# fatteningFarm.net
KiCad netlist of a schematic drawn in EAGLE
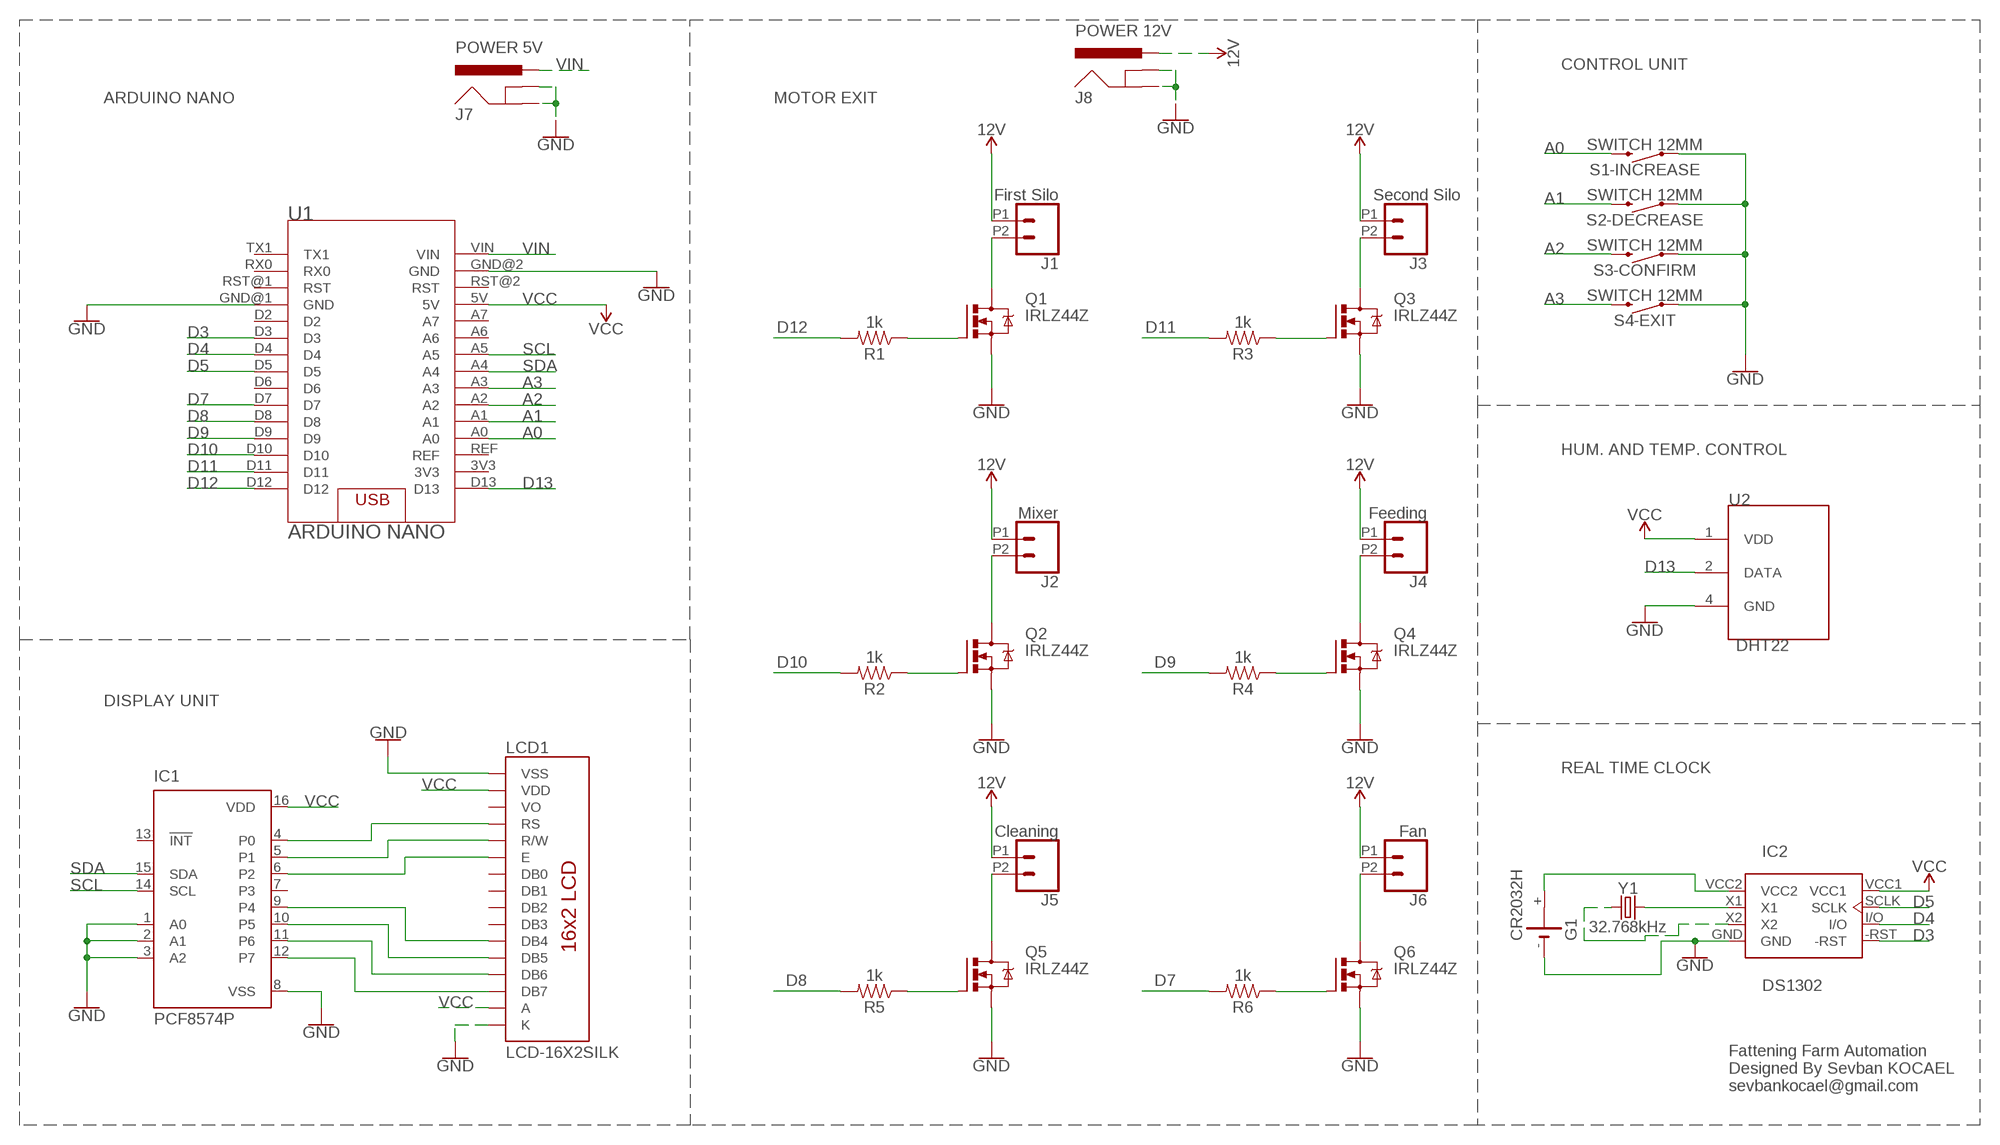
[diagram p0: schematic, sheet 1]

(export (version "E")
  (design (tool "Eeschema 10.0.6"))
  (components
    (comp (ref "G1")
      (value "CR2032H")
      (footprint "eagle-import:CR2032H")
      (libsource (lib "eagle-import") (part "CR2032H"))
    )
    (comp (ref "IC1")
      (value "PCF8574P")
      (footprint "eagle-import:DIL16")
      (fields (field (name "MPN") "PCF8574PN"))
      (libsource (lib "eagle-import") (part "PCF8574P"))
    )
    (comp (ref "IC2")
      (value "DS1302")
      (footprint "eagle-import:DIL08")
      (libsource (lib "eagle-import") (part "DS1302"))
    )
    (comp (ref "J1")
      (value "First Silo")
      (footprint "eagle-import:1X02_2.54_SCREWTERM")
      (libsource (lib "eagle-import") (part "CONN_022.54MM_SCREWTERM"))
    )
    (comp (ref "J2")
      (value "Mixer")
      (footprint "eagle-import:1X02_2.54_SCREWTERM")
      (libsource (lib "eagle-import") (part "CONN_022.54MM_SCREWTERM"))
    )
    (comp (ref "J3")
      (value "Second Silo")
      (footprint "eagle-import:1X02_2.54_SCREWTERM")
      (libsource (lib "eagle-import") (part "CONN_022.54MM_SCREWTERM"))
    )
    (comp (ref "J4")
      (value "Feeding")
      (footprint "eagle-import:1X02_2.54_SCREWTERM")
      (libsource (lib "eagle-import") (part "CONN_022.54MM_SCREWTERM"))
    )
    (comp (ref "J5")
      (value "Cleaning")
      (footprint "eagle-import:1X02_2.54_SCREWTERM")
      (libsource (lib "eagle-import") (part "CONN_022.54MM_SCREWTERM"))
    )
    (comp (ref "J6")
      (value "Fan")
      (footprint "eagle-import:1X02_2.54_SCREWTERM")
      (libsource (lib "eagle-import") (part "CONN_022.54MM_SCREWTERM"))
    )
    (comp (ref "J7")
      (value "POWER 5V")
      (footprint "eagle-import:POWER_JACK_PTH")
      (libsource (lib "eagle-import") (part "POWER_JACK"))
    )
    (comp (ref "J8")
      (value "POWER 12V")
      (footprint "eagle-import:POWER_JACK_PTH")
      (libsource (lib "eagle-import") (part "POWER_JACK"))
    )
    (comp (ref "LCD1")
      (value "LCD-16X2SILK")
      (footprint "eagle-import:LCD-16X2")
      (libsource (lib "eagle-import") (part "LCD-16X2SILK"))
    )
    (comp (ref "Q1")
      (value "IRLZ44Z")
      (footprint "eagle-import:TO220BH")
      (libsource (lib "eagle-import") (part "IRLZ44Z"))
    )
    (comp (ref "Q2")
      (value "IRLZ44Z")
      (footprint "eagle-import:TO220BH")
      (libsource (lib "eagle-import") (part "IRLZ44Z"))
    )
    (comp (ref "Q3")
      (value "IRLZ44Z")
      (footprint "eagle-import:TO220BH")
      (libsource (lib "eagle-import") (part "IRLZ44Z"))
    )
    (comp (ref "Q4")
      (value "IRLZ44Z")
      (footprint "eagle-import:TO220BH")
      (libsource (lib "eagle-import") (part "IRLZ44Z"))
    )
    (comp (ref "Q5")
      (value "IRLZ44Z")
      (footprint "eagle-import:TO220BH")
      (libsource (lib "eagle-import") (part "IRLZ44Z"))
    )
    (comp (ref "Q6")
      (value "IRLZ44Z")
      (footprint "eagle-import:TO220BH")
      (libsource (lib "eagle-import") (part "IRLZ44Z"))
    )
    (comp (ref "R1")
      (value "1k")
      (footprint "eagle-import:AXIAL-0.3")
      (libsource (lib "eagle-import") (part "1KOHM-HORIZ-1/4W-5%"))
    )
    (comp (ref "R2")
      (value "1k")
      (footprint "eagle-import:AXIAL-0.3")
      (libsource (lib "eagle-import") (part "1KOHM-HORIZ-1/4W-5%"))
    )
    (comp (ref "R3")
      (value "1k")
      (footprint "eagle-import:AXIAL-0.3")
      (libsource (lib "eagle-import") (part "1KOHM-HORIZ-1/4W-5%"))
    )
    (comp (ref "R4")
      (value "1k")
      (footprint "eagle-import:AXIAL-0.3")
      (libsource (lib "eagle-import") (part "1KOHM-HORIZ-1/4W-5%"))
    )
    (comp (ref "R5")
      (value "1k")
      (footprint "eagle-import:AXIAL-0.3")
      (libsource (lib "eagle-import") (part "1KOHM-HORIZ-1/4W-5%"))
    )
    (comp (ref "R6")
      (value "1k")
      (footprint "eagle-import:AXIAL-0.3")
      (libsource (lib "eagle-import") (part "1KOHM-HORIZ-1/4W-5%"))
    )
    (comp (ref "S1-INCREASE")
      (value "SWITCH 12MM")
      (footprint "eagle-import:TACTILE_SWITCH_PTH_12MM")
      (libsource (lib "eagle-import") (part "MOMENTARY-SWITCH-SPST-PTH-12MM"))
    )
    (comp (ref "S2-DECREASE")
      (value "SWITCH 12MM")
      (footprint "eagle-import:TACTILE_SWITCH_PTH_12MM")
      (libsource (lib "eagle-import") (part "MOMENTARY-SWITCH-SPST-PTH-12MM"))
    )
    (comp (ref "S3-CONFIRM")
      (value "SWITCH 12MM")
      (footprint "eagle-import:TACTILE_SWITCH_PTH_12MM")
      (libsource (lib "eagle-import") (part "MOMENTARY-SWITCH-SPST-PTH-12MM"))
    )
    (comp (ref "S4-EXIT")
      (value "SWITCH 12MM")
      (footprint "eagle-import:TACTILE_SWITCH_PTH_12MM")
      (libsource (lib "eagle-import") (part "MOMENTARY-SWITCH-SPST-PTH-12MM"))
    )
    (comp (ref "U1")
      (value "ARDUINO NANO")
      (footprint "eagle-import:ARDUINO_NANO")
      (libsource (lib "eagle-import") (part "ARDUINO_NANO"))
    )
    (comp (ref "U2")
      (value "DHT22")
      (footprint "eagle-import:DHT22")
      (libsource (lib "eagle-import") (part "DHT22"))
    )
    (comp (ref "Y1")
      (value "32.768kHz")
      (footprint "eagle-import:CRYSTAL-PTH-2X6-CYL")
      (libsource (lib "eagle-import") (part "CRYSTAL-32.768KHZPTH-2X6"))
    )
  )
  (nets
    (net (code "1") (name "/A0") (class "Default")
      (node (ref "S1-INCREASE") (pin "3") (pinfunction "2_3") (pintype "passive"))
      (node (ref "U1") (pin "A0") (pinfunction "A0_A0") (pintype "bidirectional"))
    )
    (net (code "2") (name "/A1") (class "Default")
      (node (ref "S2-DECREASE") (pin "3") (pinfunction "2_3") (pintype "passive"))
      (node (ref "U1") (pin "A1") (pinfunction "A1_A1") (pintype "bidirectional"))
    )
    (net (code "3") (name "/A2") (class "Default")
      (node (ref "S3-CONFIRM") (pin "3") (pinfunction "2_3") (pintype "passive"))
      (node (ref "U1") (pin "A2") (pinfunction "A2_A2") (pintype "bidirectional"))
    )
    (net (code "4") (name "/A3") (class "Default")
      (node (ref "S4-EXIT") (pin "3") (pinfunction "2_3") (pintype "passive"))
      (node (ref "U1") (pin "A3") (pinfunction "A3_A3") (pintype "bidirectional"))
    )
    (net (code "5") (name "/D3") (class "Default")
      (node (ref "IC2") (pin "-RST") (pinfunction "-RST_-RST") (pintype "bidirectional"))
      (node (ref "U1") (pin "D3") (pinfunction "D3_D3") (pintype "bidirectional"))
    )
    (net (code "6") (name "/D4") (class "Default")
      (node (ref "IC2") (pin "I/O") (pinfunction "I/O_I/O") (pintype "bidirectional"))
      (node (ref "U1") (pin "D4") (pinfunction "D4_D4") (pintype "bidirectional"))
    )
    (net (code "7") (name "/D5") (class "Default")
      (node (ref "IC2") (pin "SCLK") (pinfunction "SCLK_SCLK") (pintype "tri_state"))
      (node (ref "U1") (pin "D5") (pinfunction "D5_D5") (pintype "bidirectional"))
    )
    (net (code "8") (name "/D7") (class "Default")
      (node (ref "R6") (pin "P$2") (pinfunction "2_P$2") (pintype "passive"))
      (node (ref "U1") (pin "D7") (pinfunction "D7_D7") (pintype "bidirectional"))
    )
    (net (code "9") (name "/D8") (class "Default")
      (node (ref "R5") (pin "P$2") (pinfunction "2_P$2") (pintype "passive"))
      (node (ref "U1") (pin "D8") (pinfunction "D8_D8") (pintype "bidirectional"))
    )
    (net (code "10") (name "/D9") (class "Default")
      (node (ref "R4") (pin "P$2") (pinfunction "2_P$2") (pintype "passive"))
      (node (ref "U1") (pin "D9") (pinfunction "D9_D9") (pintype "bidirectional"))
    )
    (net (code "11") (name "/D10") (class "Default")
      (node (ref "R2") (pin "P$2") (pinfunction "2_P$2") (pintype "passive"))
      (node (ref "U1") (pin "D10") (pinfunction "D10_D10") (pintype "bidirectional"))
    )
    (net (code "12") (name "/D11") (class "Default")
      (node (ref "R3") (pin "P$2") (pinfunction "2_P$2") (pintype "passive"))
      (node (ref "U1") (pin "D11") (pinfunction "D11_D11") (pintype "bidirectional"))
    )
    (net (code "13") (name "/D12") (class "Default")
      (node (ref "R1") (pin "P$2") (pinfunction "2_P$2") (pintype "passive"))
      (node (ref "U1") (pin "D12") (pinfunction "D12_D12") (pintype "bidirectional"))
    )
    (net (code "14") (name "/D13") (class "Default")
      (node (ref "U1") (pin "D13") (pinfunction "D13_D13") (pintype "bidirectional"))
      (node (ref "U2") (pin "2") (pinfunction "DATA_2") (pintype "bidirectional"))
    )
    (net (code "15") (name "/SCL") (class "Default")
      (node (ref "IC1") (pin "14") (pinfunction "SCL_14") (pintype "input"))
      (node (ref "U1") (pin "A5") (pinfunction "A5_A5") (pintype "bidirectional"))
    )
    (net (code "16") (name "/SDA") (class "Default")
      (node (ref "IC1") (pin "15") (pinfunction "SDA_15") (pintype "bidirectional"))
      (node (ref "U1") (pin "A4") (pinfunction "A4_A4") (pintype "bidirectional"))
    )
    (net (code "17") (name "/VIN") (class "Default")
      (node (ref "J7") (pin "PWR") (pinfunction "PWR_PWR") (pintype "bidirectional"))
      (node (ref "U1") (pin "VIN") (pinfunction "VIN_VIN") (pintype "bidirectional"))
    )
    (net (code "18") (name "12V") (class "Default")
      (node (ref "J1") (pin "P1") (pinfunction "1_P1") (pintype "passive"))
      (node (ref "J2") (pin "P1") (pinfunction "1_P1") (pintype "passive"))
      (node (ref "J3") (pin "P1") (pinfunction "1_P1") (pintype "passive"))
      (node (ref "J4") (pin "P1") (pinfunction "1_P1") (pintype "passive"))
      (node (ref "J5") (pin "P1") (pinfunction "1_P1") (pintype "passive"))
      (node (ref "J6") (pin "P1") (pinfunction "1_P1") (pintype "passive"))
      (node (ref "J8") (pin "PWR") (pinfunction "PWR_PWR") (pintype "bidirectional"))
    )
    (net (code "19") (name "GND") (class "Default")
      (node (ref "G1") (pin "-") (pinfunction "-_-") (pintype "passive"))
      (node (ref "IC1") (pin "1") (pinfunction "A0_1") (pintype "input"))
      (node (ref "IC1") (pin "2") (pinfunction "A1_2") (pintype "input"))
      (node (ref "IC1") (pin "3") (pinfunction "A2_3") (pintype "input"))
      (node (ref "IC1") (pin "8") (pinfunction "VSS_8") (pintype "power_in"))
      (node (ref "IC2") (pin "GND") (pinfunction "GND_GND") (pintype "passive"))
      (node (ref "J7") (pin "GND") (pinfunction "GND_GND") (pintype "bidirectional"))
      (node (ref "J7") (pin "GNDBREAK") (pinfunction "GNDBREAK_GNDBREAK") (pintype "bidirectional"))
      (node (ref "J8") (pin "GND") (pinfunction "GND_GND") (pintype "bidirectional"))
      (node (ref "J8") (pin "GNDBREAK") (pinfunction "GNDBREAK_GNDBREAK") (pintype "bidirectional"))
      (node (ref "LCD1") (pin "1") (pinfunction "VSS_1") (pintype "power_in"))
      (node (ref "LCD1") (pin "16") (pinfunction "K_16") (pintype "power_in"))
      (node (ref "Q1") (pin "S") (pinfunction "S_S") (pintype "passive"))
      (node (ref "Q2") (pin "S") (pinfunction "S_S") (pintype "passive"))
      (node (ref "Q3") (pin "S") (pinfunction "S_S") (pintype "passive"))
      (node (ref "Q4") (pin "S") (pinfunction "S_S") (pintype "passive"))
      (node (ref "Q5") (pin "S") (pinfunction "S_S") (pintype "passive"))
      (node (ref "Q6") (pin "S") (pinfunction "S_S") (pintype "passive"))
      (node (ref "S1-INCREASE") (pin "1") (pinfunction "1_1") (pintype "passive"))
      (node (ref "S2-DECREASE") (pin "1") (pinfunction "1_1") (pintype "passive"))
      (node (ref "S3-CONFIRM") (pin "1") (pinfunction "1_1") (pintype "passive"))
      (node (ref "S4-EXIT") (pin "1") (pinfunction "1_1") (pintype "passive"))
      (node (ref "U1") (pin "GND@1") (pinfunction "GND_GND@1") (pintype "bidirectional"))
      (node (ref "U1") (pin "GND@2") (pinfunction "GND_GND@2") (pintype "bidirectional"))
      (node (ref "U2") (pin "4") (pinfunction "GND_4") (pintype "bidirectional"))
    )
    (net (code "20") (name "Net-(G1-Pad+)") (class "Default")
      (node (ref "G1") (pin "+") (pinfunction "+_+") (pintype "passive"))
      (node (ref "IC2") (pin "VCC2") (pinfunction "VCC2_VCC2") (pintype "power_in"))
    )
    (net (code "21") (name "Net-(IC1-P0)") (class "Default")
      (node (ref "IC1") (pin "4") (pinfunction "P0_4") (pintype "bidirectional"))
      (node (ref "LCD1") (pin "4") (pinfunction "RS_4") (pintype "input"))
    )
    (net (code "22") (name "Net-(IC1-P1)") (class "Default")
      (node (ref "IC1") (pin "5") (pinfunction "P1_5") (pintype "bidirectional"))
      (node (ref "LCD1") (pin "5") (pinfunction "R/W_5") (pintype "input"))
    )
    (net (code "23") (name "Net-(IC1-P2)") (class "Default")
      (node (ref "IC1") (pin "6") (pinfunction "P2_6") (pintype "bidirectional"))
      (node (ref "LCD1") (pin "6") (pinfunction "E_6") (pintype "input"))
    )
    (net (code "24") (name "Net-(IC1-P4)") (class "Default")
      (node (ref "IC1") (pin "9") (pinfunction "P4_9") (pintype "bidirectional"))
      (node (ref "LCD1") (pin "11") (pinfunction "DB4_11") (pintype "bidirectional"))
    )
    (net (code "25") (name "Net-(IC1-P5)") (class "Default")
      (node (ref "IC1") (pin "10") (pinfunction "P5_10") (pintype "bidirectional"))
      (node (ref "LCD1") (pin "12") (pinfunction "DB5_12") (pintype "bidirectional"))
    )
    (net (code "26") (name "Net-(IC1-P6)") (class "Default")
      (node (ref "IC1") (pin "11") (pinfunction "P6_11") (pintype "bidirectional"))
      (node (ref "LCD1") (pin "13") (pinfunction "DB6_13") (pintype "bidirectional"))
    )
    (net (code "27") (name "Net-(IC1-P7)") (class "Default")
      (node (ref "IC1") (pin "12") (pinfunction "P7_12") (pintype "bidirectional"))
      (node (ref "LCD1") (pin "14") (pinfunction "DB7_14") (pintype "bidirectional"))
    )
    (net (code "28") (name "Net-(IC2-PadX1)") (class "Default")
      (node (ref "IC2") (pin "X1") (pinfunction "X1_X1") (pintype "tri_state"))
      (node (ref "Y1") (pin "1") (pinfunction "1_1") (pintype "passive"))
    )
    (net (code "29") (name "Net-(IC2-PadX2)") (class "Default")
      (node (ref "IC2") (pin "X2") (pinfunction "X2_X2") (pintype "tri_state"))
      (node (ref "Y1") (pin "2") (pinfunction "2_2") (pintype "passive"))
    )
    (net (code "30") (name "Net-(J1-2)") (class "Default")
      (node (ref "J1") (pin "P2") (pinfunction "2_P2") (pintype "passive"))
      (node (ref "Q1") (pin "D") (pinfunction "D_D") (pintype "passive"))
    )
    (net (code "31") (name "Net-(J2-2)") (class "Default")
      (node (ref "J2") (pin "P2") (pinfunction "2_P2") (pintype "passive"))
      (node (ref "Q2") (pin "D") (pinfunction "D_D") (pintype "passive"))
    )
    (net (code "32") (name "Net-(J3-2)") (class "Default")
      (node (ref "J3") (pin "P2") (pinfunction "2_P2") (pintype "passive"))
      (node (ref "Q3") (pin "D") (pinfunction "D_D") (pintype "passive"))
    )
    (net (code "33") (name "Net-(J4-2)") (class "Default")
      (node (ref "J4") (pin "P2") (pinfunction "2_P2") (pintype "passive"))
      (node (ref "Q4") (pin "D") (pinfunction "D_D") (pintype "passive"))
    )
    (net (code "34") (name "Net-(J5-2)") (class "Default")
      (node (ref "J5") (pin "P2") (pinfunction "2_P2") (pintype "passive"))
      (node (ref "Q5") (pin "D") (pinfunction "D_D") (pintype "passive"))
    )
    (net (code "35") (name "Net-(J6-2)") (class "Default")
      (node (ref "J6") (pin "P2") (pinfunction "2_P2") (pintype "passive"))
      (node (ref "Q6") (pin "D") (pinfunction "D_D") (pintype "passive"))
    )
    (net (code "36") (name "Net-(R1-1)") (class "Default")
      (node (ref "Q1") (pin "G") (pinfunction "G_G") (pintype "passive"))
      (node (ref "R1") (pin "P$1") (pinfunction "1_P$1") (pintype "passive"))
    )
    (net (code "37") (name "Net-(R2-1)") (class "Default")
      (node (ref "Q2") (pin "G") (pinfunction "G_G") (pintype "passive"))
      (node (ref "R2") (pin "P$1") (pinfunction "1_P$1") (pintype "passive"))
    )
    (net (code "38") (name "Net-(R3-1)") (class "Default")
      (node (ref "Q3") (pin "G") (pinfunction "G_G") (pintype "passive"))
      (node (ref "R3") (pin "P$1") (pinfunction "1_P$1") (pintype "passive"))
    )
    (net (code "39") (name "Net-(R4-1)") (class "Default")
      (node (ref "Q4") (pin "G") (pinfunction "G_G") (pintype "passive"))
      (node (ref "R4") (pin "P$1") (pinfunction "1_P$1") (pintype "passive"))
    )
    (net (code "40") (name "Net-(R5-1)") (class "Default")
      (node (ref "Q5") (pin "G") (pinfunction "G_G") (pintype "passive"))
      (node (ref "R5") (pin "P$1") (pinfunction "1_P$1") (pintype "passive"))
    )
    (net (code "41") (name "Net-(R6-1)") (class "Default")
      (node (ref "Q6") (pin "G") (pinfunction "G_G") (pintype "passive"))
      (node (ref "R6") (pin "P$1") (pinfunction "1_P$1") (pintype "passive"))
    )
    (net (code "42") (name "VCC") (class "Default")
      (node (ref "IC1") (pin "16") (pinfunction "VDD_16") (pintype "power_in"))
      (node (ref "IC2") (pin "VCC1") (pinfunction "VCC1_VCC1") (pintype "power_in"))
      (node (ref "LCD1") (pin "15") (pinfunction "A_15") (pintype "power_in"))
      (node (ref "LCD1") (pin "2") (pinfunction "VDD_2") (pintype "power_in"))
      (node (ref "U1") (pin "5V") (pinfunction "5V_5V") (pintype "bidirectional"))
      (node (ref "U2") (pin "1") (pinfunction "VDD_1") (pintype "bidirectional"))
    )
    (net (code "43") (name "unconnected-(G1-+-Pad+@1)") (class "Default")
      (node (ref "G1") (pin "+@1") (pinfunction "+_+@1") (pintype "passive"))
    )
    (net (code "44") (name "unconnected-(IC1-P3-Pad7)") (class "Default")
      (node (ref "IC1") (pin "7") (pinfunction "P3_7") (pintype "bidirectional"))
    )
    (net (code "45") (name "unconnected-(IC1-~{INT}-Pad13)") (class "Default")
      (node (ref "IC1") (pin "13") (pinfunction "~{INT}_13") (pintype "output"))
    )
    (net (code "46") (name "unconnected-(LCD1-DB0-Pad7)") (class "Default")
      (node (ref "LCD1") (pin "7") (pinfunction "DB0_7") (pintype "bidirectional"))
    )
    (net (code "47") (name "unconnected-(LCD1-DB1-Pad8)") (class "Default")
      (node (ref "LCD1") (pin "8") (pinfunction "DB1_8") (pintype "bidirectional"))
    )
    (net (code "48") (name "unconnected-(LCD1-DB2-Pad9)") (class "Default")
      (node (ref "LCD1") (pin "9") (pinfunction "DB2_9") (pintype "bidirectional"))
    )
    (net (code "49") (name "unconnected-(LCD1-DB3-Pad10)") (class "Default")
      (node (ref "LCD1") (pin "10") (pinfunction "DB3_10") (pintype "bidirectional"))
    )
    (net (code "50") (name "unconnected-(LCD1-VO-Pad3)") (class "Default")
      (node (ref "LCD1") (pin "3") (pinfunction "VO_3") (pintype "bidirectional"))
    )
    (net (code "51") (name "unconnected-(U1-Pad3V3)") (class "Default")
      (node (ref "U1") (pin "3V3") (pinfunction "3V3_3V3") (pintype "bidirectional"))
    )
    (net (code "52") (name "unconnected-(U1-PadA6)") (class "Default")
      (node (ref "U1") (pin "A6") (pinfunction "A6_A6") (pintype "bidirectional"))
    )
    (net (code "53") (name "unconnected-(U1-PadA7)") (class "Default")
      (node (ref "U1") (pin "A7") (pinfunction "A7_A7") (pintype "bidirectional"))
    )
    (net (code "54") (name "unconnected-(U1-PadD2)") (class "Default")
      (node (ref "U1") (pin "D2") (pinfunction "D2_D2") (pintype "bidirectional"))
    )
    (net (code "55") (name "unconnected-(U1-PadD6)") (class "Default")
      (node (ref "U1") (pin "D6") (pinfunction "D6_D6") (pintype "bidirectional"))
    )
    (net (code "56") (name "unconnected-(U1-PadREF)") (class "Default")
      (node (ref "U1") (pin "REF") (pinfunction "REF_REF") (pintype "bidirectional"))
    )
    (net (code "57") (name "unconnected-(U1-PadRX0)") (class "Default")
      (node (ref "U1") (pin "RX0") (pinfunction "RX0_RX0") (pintype "bidirectional"))
    )
    (net (code "58") (name "unconnected-(U1-PadTX1)") (class "Default")
      (node (ref "U1") (pin "TX1") (pinfunction "TX1_TX1") (pintype "bidirectional"))
    )
    (net (code "59") (name "unconnected-(U1-RST-PadRST@1)") (class "Default")
      (node (ref "U1") (pin "RST@1") (pinfunction "RST_RST@1") (pintype "bidirectional"))
    )
    (net (code "60") (name "unconnected-(U1-RST-PadRST@2)") (class "Default")
      (node (ref "U1") (pin "RST@2") (pinfunction "RST_RST@2") (pintype "bidirectional"))
    )
  )
)
